# Buck_Converter.net
KiCad netlist of a schematic drawn in Altium Designer
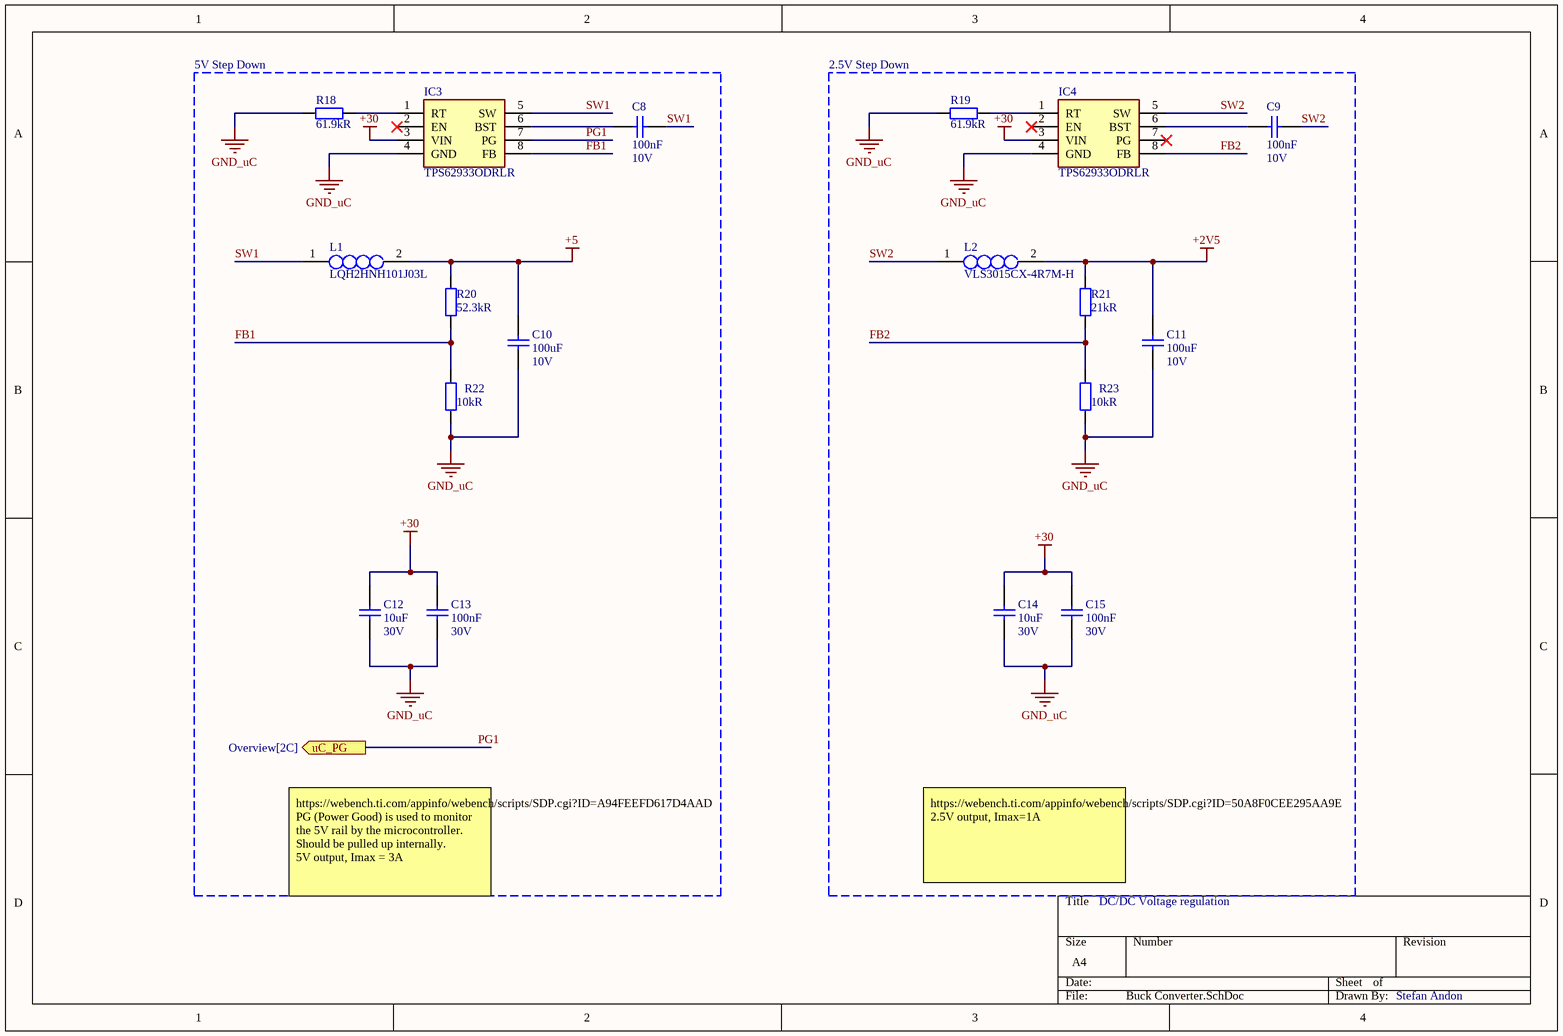
[diagram p0: Buck Converter.SchDoc]

(export (version "E")
  (design (tool "Eeschema 10.0.6"))
  (components
    (comp (ref "C8")
      (value "100nF")
      (footprint "CAP_0603")
      (description "SMD Capacitor")
      (fields
        (field (name "TOLERANCE") "tbd")
        (field (name "VOLTAGE") "10V")
        (field (name "Comment") "Capacitor_SMD")
      )
      (libsource (lib "TUfast e") (part "SMD Capacitor"))
    )
    (comp (ref "C9")
      (value "100nF")
      (footprint "CAP_0603")
      (description "SMD Capacitor")
      (fields
        (field (name "TOLERANCE") "tbd")
        (field (name "VOLTAGE") "10V")
        (field (name "Comment") "Capacitor_SMD")
      )
      (libsource (lib "TUfast e") (part "SMD Capacitor"))
    )
    (comp (ref "C10")
      (value "100uF")
      (footprint "CAP_0603")
      (description "SMD Capacitor")
      (fields
        (field (name "TOLERANCE") "tbd")
        (field (name "VOLTAGE") "10V")
        (field (name "Comment") "Capacitor_SMD")
      )
      (libsource (lib "TUfast e") (part "SMD Capacitor"))
    )
    (comp (ref "C11")
      (value "100uF")
      (footprint "CAP_0603")
      (description "SMD Capacitor")
      (fields
        (field (name "TOLERANCE") "tbd")
        (field (name "VOLTAGE") "10V")
        (field (name "Comment") "Capacitor_SMD")
      )
      (libsource (lib "TUfast e") (part "SMD Capacitor"))
    )
    (comp (ref "C12")
      (value "10uF")
      (footprint "CAP_0603")
      (description "SMD Capacitor")
      (fields
        (field (name "TOLERANCE") "tbd")
        (field (name "VOLTAGE") "30V")
        (field (name "Comment") "Capacitor_SMD")
      )
      (libsource (lib "TUfast e") (part "SMD Capacitor"))
    )
    (comp (ref "C13")
      (value "100nF")
      (footprint "CAP_0603")
      (description "SMD Capacitor")
      (fields
        (field (name "TOLERANCE") "tbd")
        (field (name "VOLTAGE") "30V")
        (field (name "Comment") "Capacitor_SMD")
      )
      (libsource (lib "TUfast e") (part "SMD Capacitor"))
    )
    (comp (ref "C14")
      (value "10uF")
      (footprint "CAP_0603")
      (description "SMD Capacitor")
      (fields
        (field (name "TOLERANCE") "tbd")
        (field (name "VOLTAGE") "30V")
        (field (name "Comment") "Capacitor_SMD")
      )
      (libsource (lib "TUfast e") (part "SMD Capacitor"))
    )
    (comp (ref "C15")
      (value "100nF")
      (footprint "CAP_0603")
      (description "SMD Capacitor")
      (fields
        (field (name "TOLERANCE") "tbd")
        (field (name "VOLTAGE") "30V")
        (field (name "Comment") "Capacitor_SMD")
      )
      (libsource (lib "TUfast e") (part "SMD Capacitor"))
    )
    (comp (ref "IC3")
      (value "TPS62933ODRLR")
      (footprint "SamacSys:SOTFL50P160X60-8N")
      (description "Integrated Circuit")
      (fields (field (name "MOUSER PART NUMBER") "595-TPS62933ODRLR"))
      (libsource (lib "*") (part "TPS62933ODRLR"))
    )
    (comp (ref "IC4")
      (value "TPS62933ODRLR")
      (footprint "SamacSys:SOTFL50P160X60-8N")
      (description "Integrated Circuit")
      (fields (field (name "MOUSER PART NUMBER") "595-TPS62933ODRLR"))
      (libsource (lib "*") (part "TPS62933ODRLR"))
    )
    (comp (ref "L1")
      (value "LQH2HNH101J03L")
      (footprint "SamacSys:LQH2HNH100J03L")
      (description "Inductor")
      (fields (field (name "MOUSER PART NUMBER") "81-LQH2HNH101J03L"))
      (libsource (lib "*") (part "LQH2HNH101J03L"))
    )
    (comp (ref "L2")
      (value "VLS3015CX-4R7M-H")
      (footprint "SamacSys:VLS3015")
      (description "Inductor")
      (fields (field (name "MOUSER PART NUMBER") "810-VLS3015CX-4R7M-H"))
      (libsource (lib "*") (part "VLS3015CX-4R7M-H"))
    )
    (comp (ref "R18")
      (value "61.9kR")
      (footprint "RES_0603")
      (fields
        (field (name "TOLERANCE") "tbd")
        (field (name "POWER") "7W")
        (field (name "Comment") "Resistor_SMD")
      )
      (libsource (lib "") (part "Resistor_1"))
    )
    (comp (ref "R19")
      (value "61.9kR")
      (footprint "RES_0603")
      (fields
        (field (name "TOLERANCE") "tbd")
        (field (name "POWER") "7W")
        (field (name "Comment") "Resistor_SMD")
      )
      (libsource (lib "") (part "Resistor_1"))
    )
    (comp (ref "R20")
      (value "52.3kR")
      (footprint "RES_0603")
      (fields
        (field (name "TOLERANCE") "tbd")
        (field (name "POWER") "7W")
        (field (name "Comment") "Resistor_SMD")
      )
      (libsource (lib "TUfast e") (part "Resistor"))
    )
    (comp (ref "R21")
      (value "21kR")
      (footprint "RES_0603")
      (fields
        (field (name "TOLERANCE") "tbd")
        (field (name "POWER") "7W")
        (field (name "Comment") "Resistor_SMD")
      )
      (libsource (lib "TUfast e") (part "Resistor"))
    )
    (comp (ref "R22")
      (value "10kR")
      (footprint "RES_0603")
      (fields
        (field (name "TOLERANCE") "tbd")
        (field (name "POWER") "7W")
        (field (name "Comment") "Resistor_SMD")
      )
      (libsource (lib "TUfast e") (part "Resistor"))
    )
    (comp (ref "R23")
      (value "10kR")
      (footprint "RES_0603")
      (fields
        (field (name "TOLERANCE") "tbd")
        (field (name "POWER") "7W")
        (field (name "Comment") "Resistor_SMD")
      )
      (libsource (lib "TUfast e") (part "Resistor"))
    )
  )
  (nets
    (net (code "1") (name "+2V5") (class "Default")
      (node (ref "C11") (pin "2") (pinfunction "2_2") (pintype "passive"))
      (node (ref "L2") (pin "2") (pinfunction "2_2") (pintype "passive"))
      (node (ref "R21") (pin "1") (pinfunction "1_1") (pintype "passive"))
    )
    (net (code "2") (name "+5") (class "Default")
      (node (ref "C10") (pin "2") (pinfunction "2_2") (pintype "passive"))
      (node (ref "L1") (pin "2") (pinfunction "2_2") (pintype "passive"))
      (node (ref "R20") (pin "1") (pinfunction "1_1") (pintype "passive"))
    )
    (net (code "3") (name "+30") (class "Default")
      (node (ref "C12") (pin "2") (pinfunction "2_2") (pintype "passive"))
      (node (ref "C13") (pin "2") (pinfunction "2_2") (pintype "passive"))
      (node (ref "C14") (pin "2") (pinfunction "2_2") (pintype "passive"))
      (node (ref "C15") (pin "2") (pinfunction "2_2") (pintype "passive"))
      (node (ref "IC3") (pin "3") (pinfunction "VIN_3") (pintype "passive"))
      (node (ref "IC4") (pin "3") (pinfunction "VIN_3") (pintype "passive"))
    )
    (net (code "4") (name "/FB1") (class "Default")
      (node (ref "IC3") (pin "8") (pinfunction "FB_8") (pintype "passive"))
      (node (ref "R20") (pin "2") (pinfunction "2_2") (pintype "passive"))
      (node (ref "R22") (pin "1") (pinfunction "1_1") (pintype "passive"))
    )
    (net (code "5") (name "/FB2") (class "Default")
      (node (ref "IC4") (pin "8") (pinfunction "FB_8") (pintype "passive"))
      (node (ref "R21") (pin "2") (pinfunction "2_2") (pintype "passive"))
      (node (ref "R23") (pin "1") (pinfunction "1_1") (pintype "passive"))
    )
    (net (code "6") (name "/PG1") (class "Default")
      (node (ref "IC3") (pin "7") (pinfunction "PG_7") (pintype "passive"))
    )
    (net (code "7") (name "/SW1") (class "Default")
      (node (ref "C8") (pin "1") (pinfunction "1_1") (pintype "passive"))
      (node (ref "IC3") (pin "5") (pinfunction "SW_5") (pintype "passive"))
      (node (ref "L1") (pin "1") (pinfunction "1_1") (pintype "passive"))
    )
    (net (code "8") (name "/SW2") (class "Default")
      (node (ref "C9") (pin "1") (pinfunction "1_1") (pintype "passive"))
      (node (ref "IC4") (pin "5") (pinfunction "SW_5") (pintype "passive"))
      (node (ref "L2") (pin "1") (pinfunction "1_1") (pintype "passive"))
    )
    (net (code "9") (name "GND_uC") (class "Default")
      (node (ref "C10") (pin "1") (pinfunction "1_1") (pintype "passive"))
      (node (ref "C11") (pin "1") (pinfunction "1_1") (pintype "passive"))
      (node (ref "C12") (pin "1") (pinfunction "1_1") (pintype "passive"))
      (node (ref "C13") (pin "1") (pinfunction "1_1") (pintype "passive"))
      (node (ref "C14") (pin "1") (pinfunction "1_1") (pintype "passive"))
      (node (ref "C15") (pin "1") (pinfunction "1_1") (pintype "passive"))
      (node (ref "IC3") (pin "4") (pinfunction "GND_4") (pintype "passive"))
      (node (ref "IC4") (pin "4") (pinfunction "GND_4") (pintype "passive"))
      (node (ref "R18") (pin "1") (pinfunction "1_1") (pintype "passive"))
      (node (ref "R19") (pin "1") (pinfunction "1_1") (pintype "passive"))
      (node (ref "R22") (pin "2") (pinfunction "2_2") (pintype "passive"))
      (node (ref "R23") (pin "2") (pinfunction "2_2") (pintype "passive"))
    )
    (net (code "10") (name "Net-(IC3-BST)") (class "Default")
      (node (ref "C8") (pin "2") (pinfunction "2_2") (pintype "passive"))
      (node (ref "IC3") (pin "6") (pinfunction "BST_6") (pintype "passive"))
    )
    (net (code "11") (name "Net-(IC3-RT)") (class "Default")
      (node (ref "IC3") (pin "1") (pinfunction "RT_1") (pintype "passive"))
      (node (ref "R18") (pin "2") (pinfunction "2_2") (pintype "passive"))
    )
    (net (code "12") (name "Net-(IC4-BST)") (class "Default")
      (node (ref "C9") (pin "2") (pinfunction "2_2") (pintype "passive"))
      (node (ref "IC4") (pin "6") (pinfunction "BST_6") (pintype "passive"))
    )
    (net (code "13") (name "Net-(IC4-RT)") (class "Default")
      (node (ref "IC4") (pin "1") (pinfunction "RT_1") (pintype "passive"))
      (node (ref "R19") (pin "2") (pinfunction "2_2") (pintype "passive"))
    )
    (net (code "14") (name "unconnected-(IC3-EN-Pad2)") (class "Default")
      (node (ref "IC3") (pin "2") (pinfunction "EN_2") (pintype "passive+no_connect"))
    )
    (net (code "15") (name "unconnected-(IC4-EN-Pad2)") (class "Default")
      (node (ref "IC4") (pin "2") (pinfunction "EN_2") (pintype "passive+no_connect"))
    )
    (net (code "16") (name "unconnected-(IC4-PG-Pad7)") (class "Default")
      (node (ref "IC4") (pin "7") (pinfunction "PG_7") (pintype "passive+no_connect"))
    )
  )
)
